# 1-Schematic_BATTERY_ELIMINATOR.net
KiCad netlist of a schematic drawn in EasyEDA
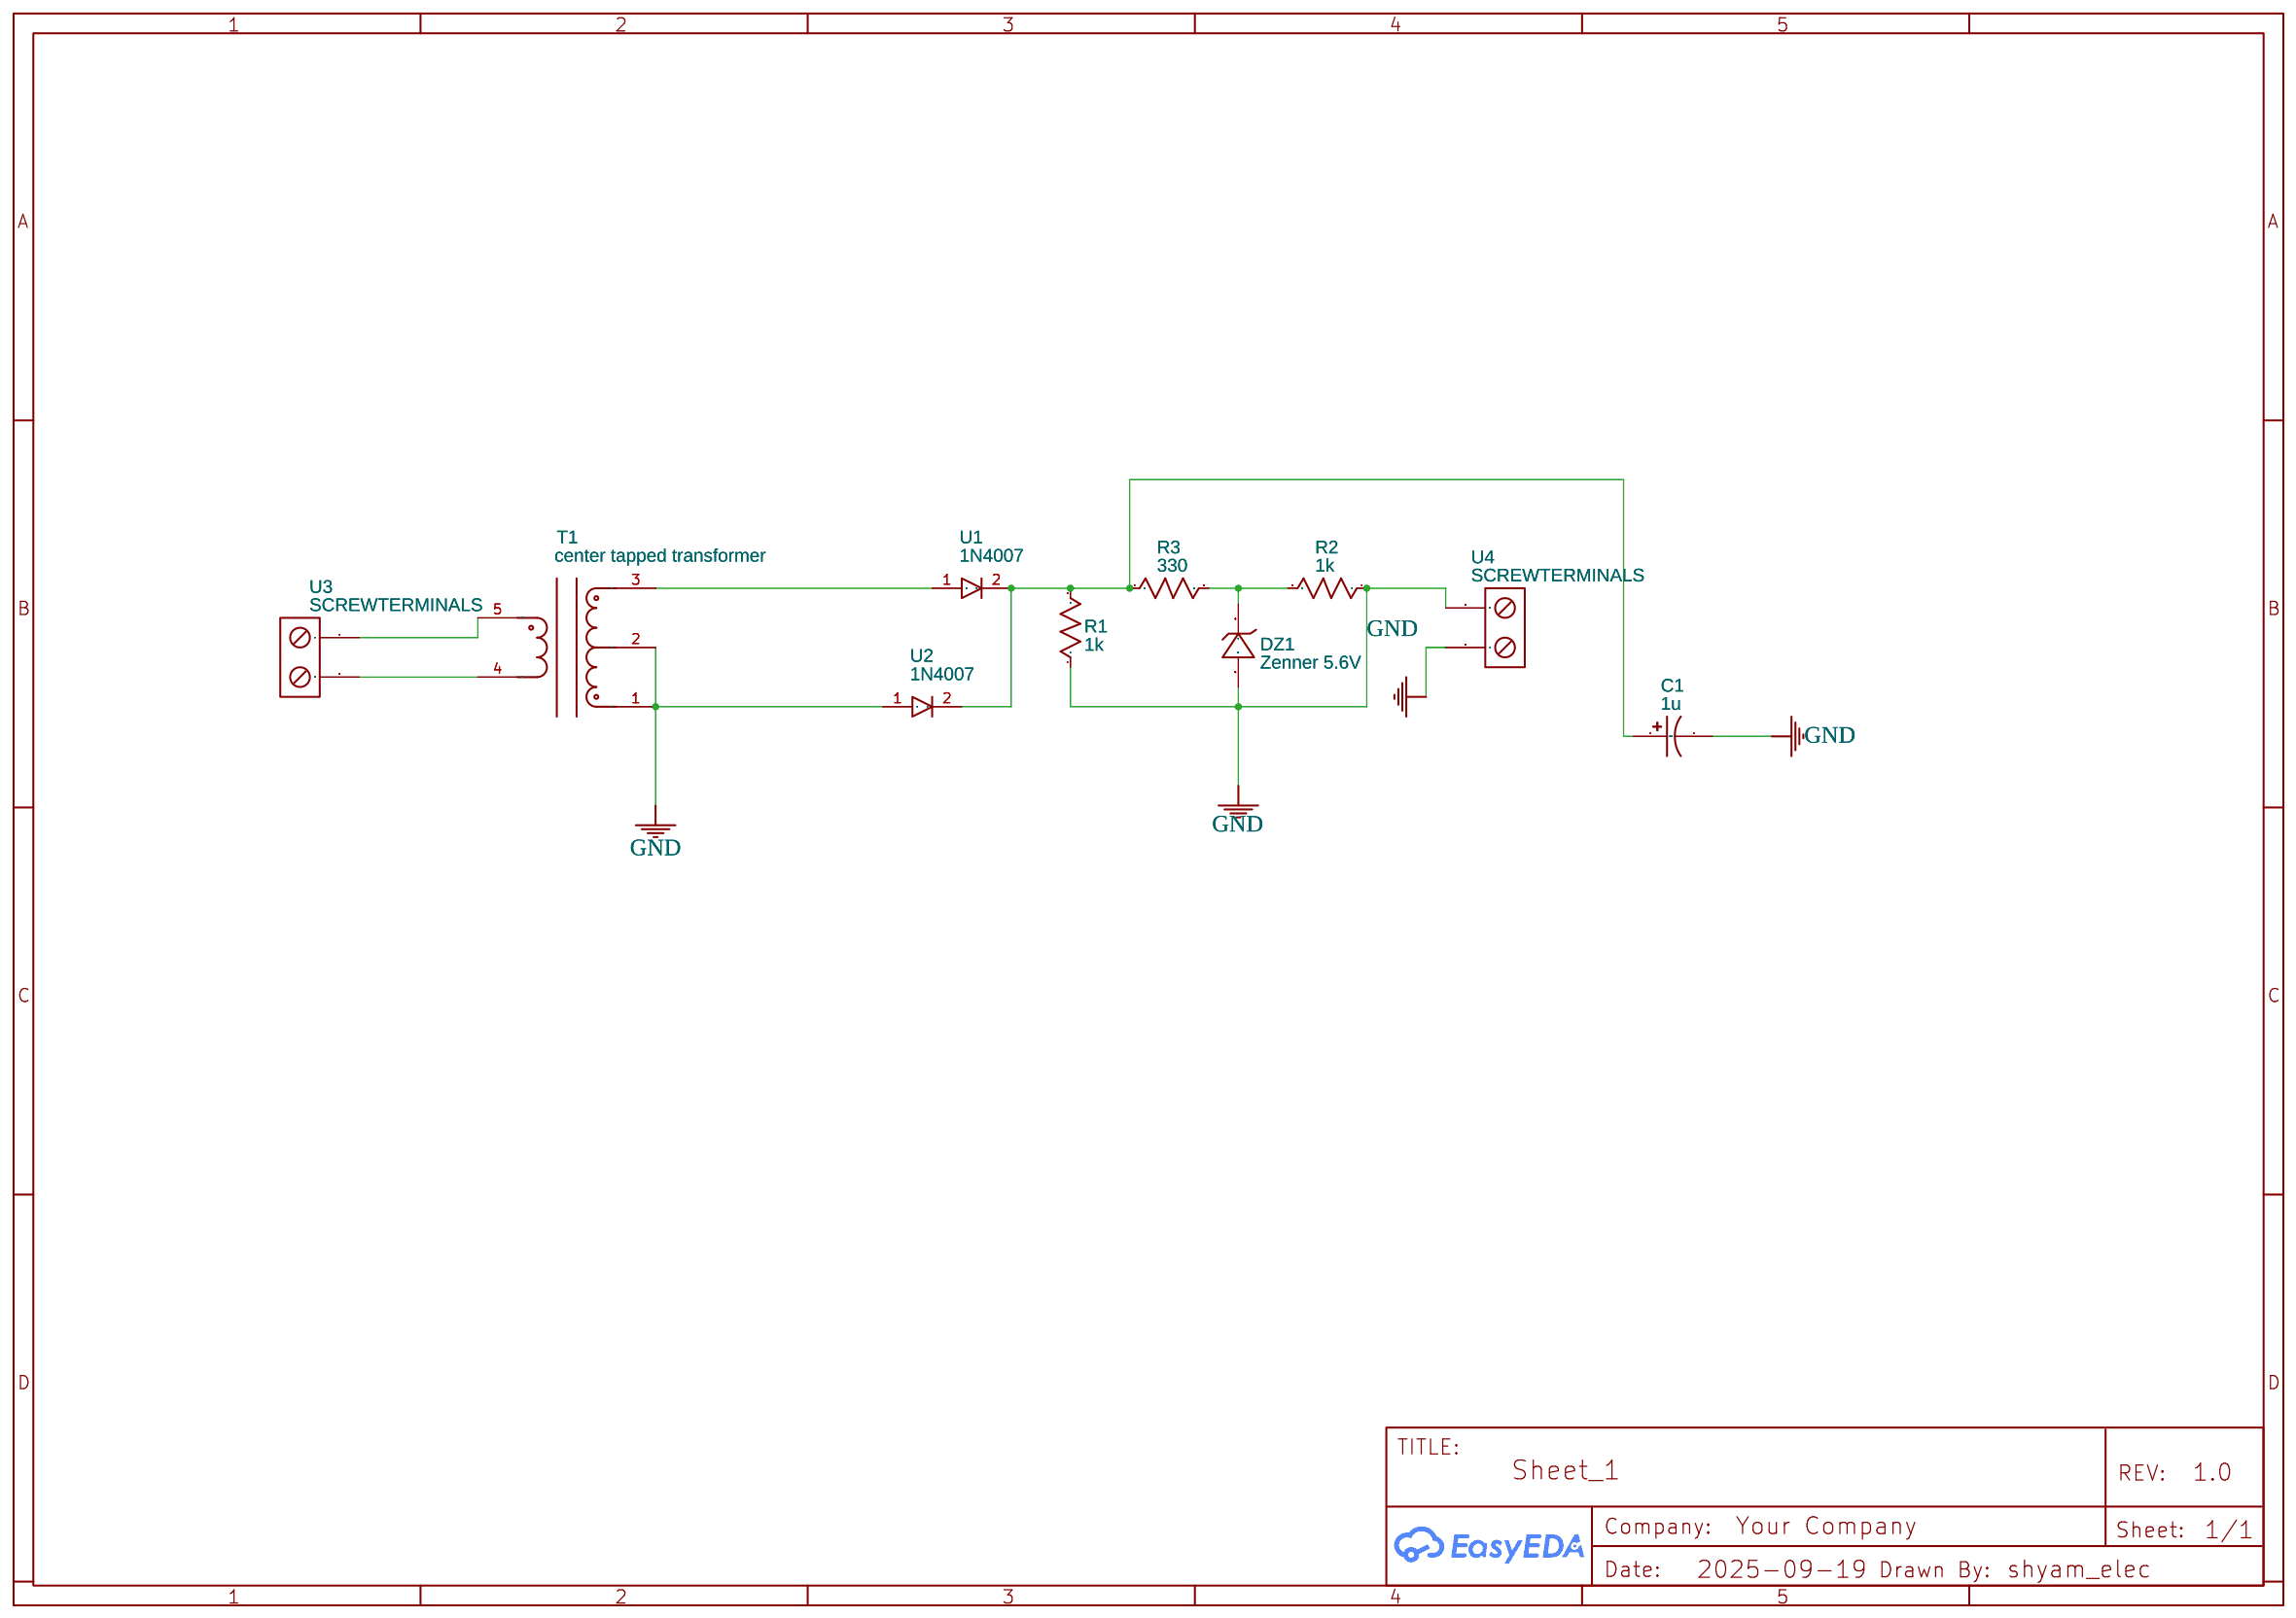
[diagram p0: schematic sheet]

(export (version "E")
  (design (tool "Eeschema 10.0.6"))
  (components
    (comp (ref "C1") (value "1u") (libsource (lib "") (part "CE_TH_D12.5×F5.0_US")))
    (comp (ref "DZ1") (value "Zenner 5.6V") (libsource (lib "") (part "Zenner 5.6V")))
    (comp (ref "R1") (value "1k") (libsource (lib "") (part "R_AXIAL-0.5_US_1")))
    (comp (ref "R2") (value "1k") (libsource (lib "") (part "R_AXIAL-0.5_US")))
    (comp (ref "R3") (value "330") (libsource (lib "") (part "R_AXIAL-0.5_US_2")))
    (comp (ref "T1")
      (value "center tapped transformer")
      (fields (field (name "Manufacturer Part") "HR051142") (field (name "Manufacturer") "HANRUN"))
      (libsource (lib "") (part "center tapped transformer"))
    )
    (comp (ref "U1") (value "1N4007") (libsource (lib "") (part "1N4007")))
    (comp (ref "U2") (value "1N4007") (libsource (lib "") (part "1N4007")))
    (comp (ref "U3") (value "SCREWTERMINALS") (libsource (lib "") (part "SCREWTERMINALS")))
    (comp (ref "U4") (value "SCREWTERMINALS") (libsource (lib "") (part "SCREWTERMINALS_1")))
  )
  (nets
    (net (code "1") (name "GND") (class "Default")
      (node (ref "C1") (pin "2") (pinfunction "2_2") (pintype "unspecified"))
      (node (ref "DZ1") (pin "P$2") (pinfunction "2_P$2") (pintype "unspecified"))
      (node (ref "R1") (pin "1") (pinfunction "1_1") (pintype "unspecified"))
      (node (ref "R2") (pin "1") (pinfunction "1_1") (pintype "unspecified"))
      (node (ref "T1") (pin "1") (pinfunction "1_1") (pintype "unspecified"))
      (node (ref "T1") (pin "2") (pinfunction "2_2") (pintype "unspecified"))
      (node (ref "U2") (pin "1") (pinfunction "1_1") (pintype "unspecified"))
      (node (ref "U4") (pin "1") (pinfunction "1_1") (pintype "unspecified"))
      (node (ref "U4") (pin "2") (pinfunction "2_2") (pintype "unspecified"))
    )
    (net (code "2") (name "Net-(C1-Pad1)") (class "Default")
      (node (ref "C1") (pin "1") (pinfunction "1_1") (pintype "unspecified"))
      (node (ref "R1") (pin "2") (pinfunction "2_2") (pintype "unspecified"))
      (node (ref "R3") (pin "1") (pinfunction "1_1") (pintype "unspecified"))
      (node (ref "U1") (pin "2") (pinfunction "2_2") (pintype "unspecified"))
      (node (ref "U2") (pin "2") (pinfunction "2_2") (pintype "unspecified"))
    )
    (net (code "3") (name "Net-(DZ1-1)") (class "Default")
      (node (ref "DZ1") (pin "P$1") (pinfunction "1_P$1") (pintype "unspecified"))
      (node (ref "R2") (pin "2") (pinfunction "2_2") (pintype "unspecified"))
      (node (ref "R3") (pin "2") (pinfunction "2_2") (pintype "unspecified"))
    )
    (net (code "4") (name "Net-(T1-Pad3)") (class "Default")
      (node (ref "T1") (pin "3") (pinfunction "3_3") (pintype "unspecified"))
      (node (ref "U1") (pin "1") (pinfunction "1_1") (pintype "unspecified"))
    )
    (net (code "5") (name "Net-(T1-Pad4)") (class "Default")
      (node (ref "T1") (pin "4") (pinfunction "4_4") (pintype "unspecified"))
      (node (ref "U3") (pin "2") (pinfunction "2_2") (pintype "unspecified"))
    )
    (net (code "6") (name "Net-(T1-Pad5)") (class "Default")
      (node (ref "T1") (pin "5") (pinfunction "5_5") (pintype "unspecified"))
      (node (ref "U3") (pin "1") (pinfunction "1_1") (pintype "unspecified"))
    )
  )
)
